# 8-Kanal-DIN-IN_V0.net
KiCad netlist of a schematic drawn in EAGLE
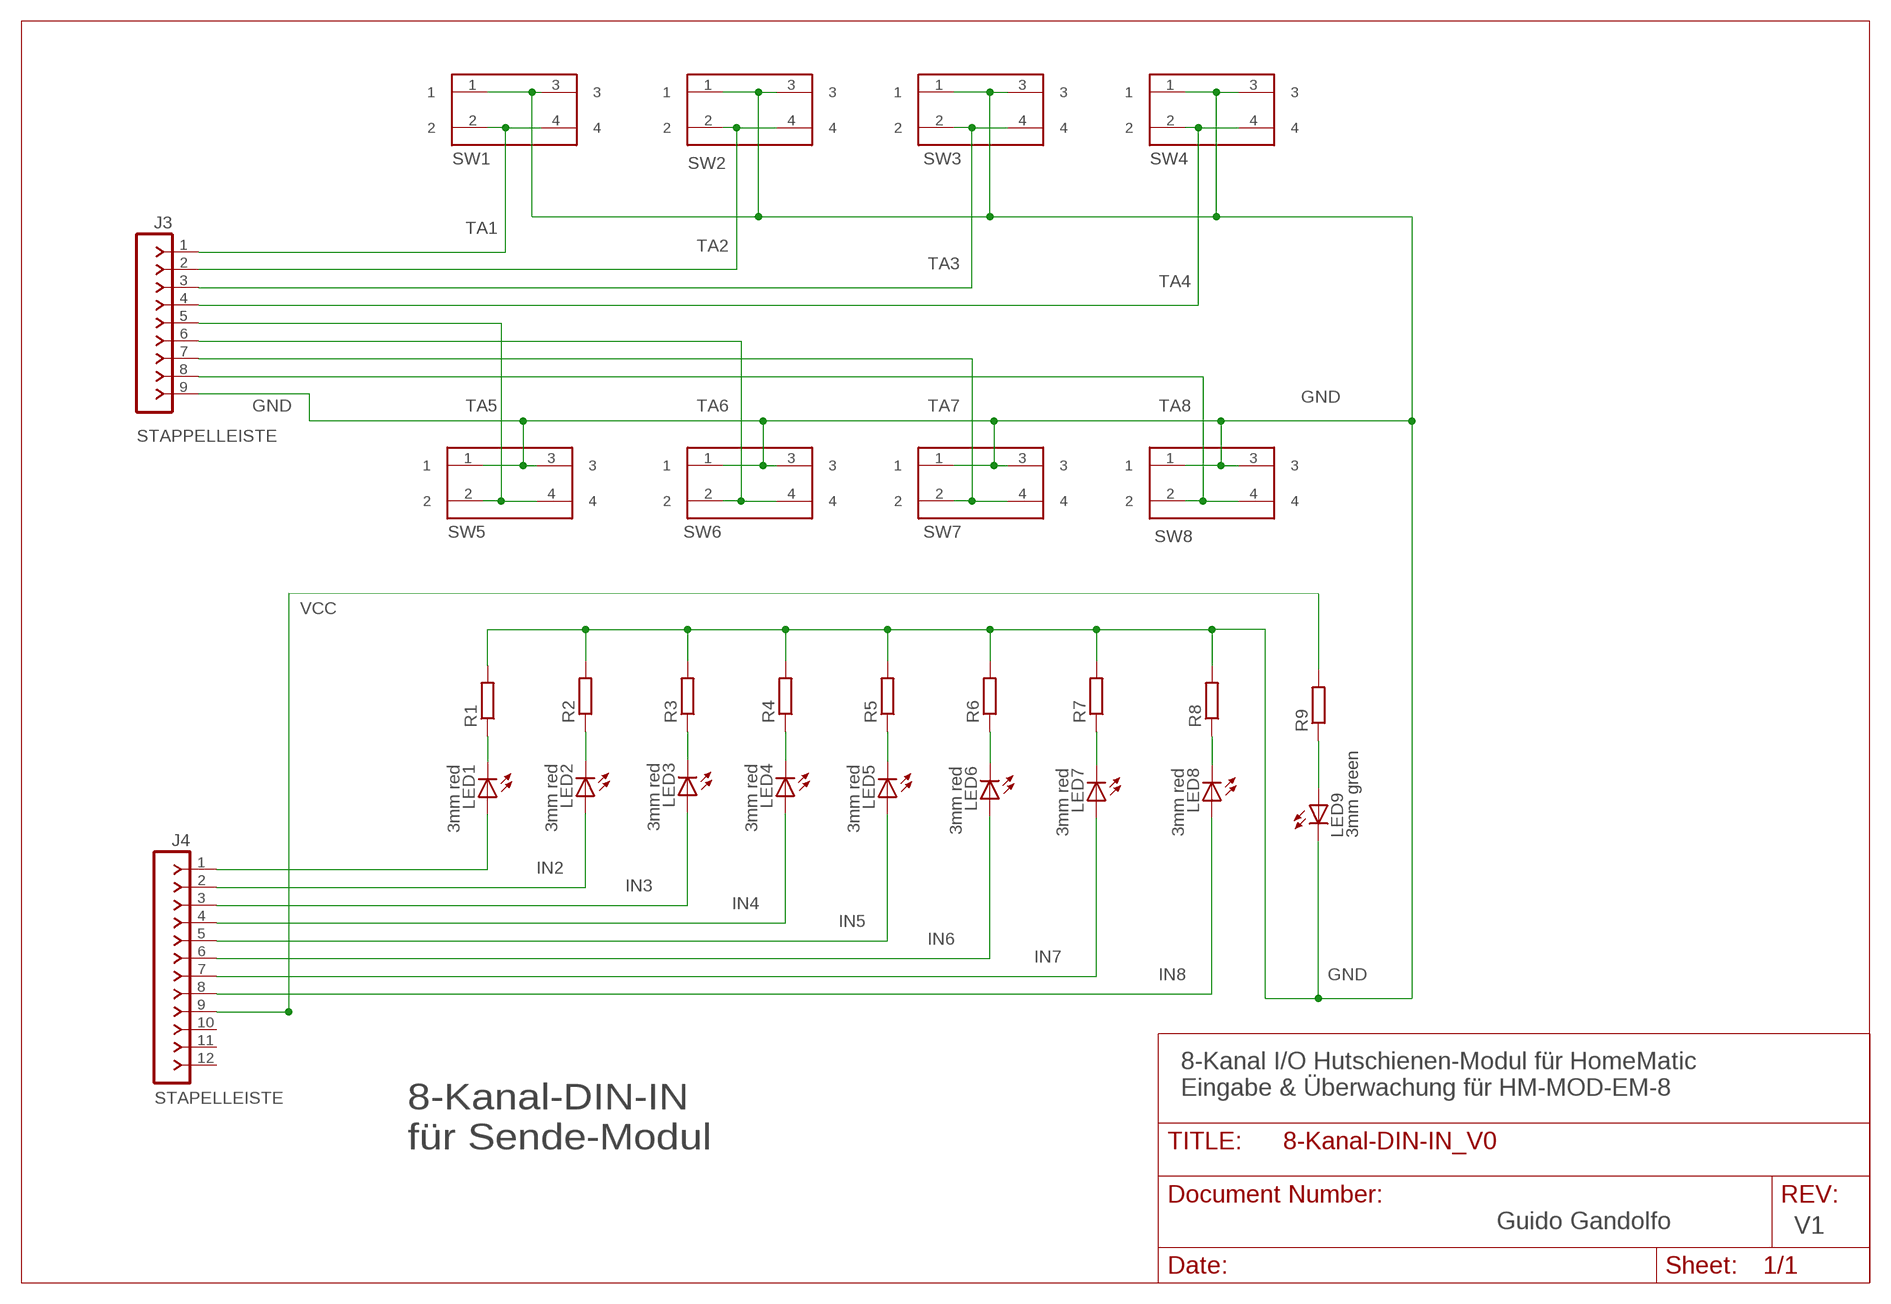
[diagram p0: schematic, sheet 1]

(export (version "E")
  (design (tool "Eeschema 10.0.6"))
  (components
    (comp (ref "J3")
      (value "STAPPELLEISTE")
      (footprint "eagle-import:SIP-100-09-40Y")
      (libsource (lib "eagle-import") (part "F-1X09-SIP-100-40Y"))
    )
    (comp (ref "J4")
      (value "STAPELLEISTE")
      (footprint "eagle-import:SIP-100-12-40Y")
      (libsource (lib "eagle-import") (part "F-1X12-SIP-100-40Y"))
    )
    (comp (ref "LED1")
      (value "3mm red")
      (footprint "eagle-import:LED3MM")
      (libsource (lib "eagle-import") (part "LED3MM"))
    )
    (comp (ref "LED2")
      (value "3mm red")
      (footprint "eagle-import:LED3MM")
      (libsource (lib "eagle-import") (part "LED3MM"))
    )
    (comp (ref "LED3")
      (value "3mm red")
      (footprint "eagle-import:LED3MM")
      (libsource (lib "eagle-import") (part "LED3MM"))
    )
    (comp (ref "LED4")
      (value "3mm red")
      (footprint "eagle-import:LED3MM")
      (libsource (lib "eagle-import") (part "LED3MM"))
    )
    (comp (ref "LED5")
      (value "3mm red")
      (footprint "eagle-import:LED3MM")
      (libsource (lib "eagle-import") (part "LED3MM"))
    )
    (comp (ref "LED6")
      (value "3mm red")
      (footprint "eagle-import:LED3MM")
      (libsource (lib "eagle-import") (part "LED3MM"))
    )
    (comp (ref "LED7")
      (value "3mm red")
      (footprint "eagle-import:LED3MM")
      (libsource (lib "eagle-import") (part "LED3MM"))
    )
    (comp (ref "LED8")
      (value "3mm red")
      (footprint "eagle-import:LED3MM")
      (libsource (lib "eagle-import") (part "LED3MM"))
    )
    (comp (ref "LED9")
      (value "3mm green")
      (footprint "eagle-import:LED3MM")
      (libsource (lib "eagle-import") (part "LED3MM"))
    )
    (comp (ref "R1")
      (value "R-EU_0207/2V")
      (footprint "eagle-import:0207_2V")
      (libsource (lib "eagle-import") (part "R-EU_0207/2V"))
    )
    (comp (ref "R2")
      (value "R-EU_0207/2V")
      (footprint "eagle-import:0207_2V")
      (libsource (lib "eagle-import") (part "R-EU_0207/2V"))
    )
    (comp (ref "R3")
      (value "R-EU_0207/2V")
      (footprint "eagle-import:0207_2V")
      (libsource (lib "eagle-import") (part "R-EU_0207/2V"))
    )
    (comp (ref "R4")
      (value "R-EU_0207/2V")
      (footprint "eagle-import:0207_2V")
      (libsource (lib "eagle-import") (part "R-EU_0207/2V"))
    )
    (comp (ref "R5")
      (value "R-EU_0207/2V")
      (footprint "eagle-import:0207_2V")
      (libsource (lib "eagle-import") (part "R-EU_0207/2V"))
    )
    (comp (ref "R6")
      (value "R-EU_0207/2V")
      (footprint "eagle-import:0207_2V")
      (libsource (lib "eagle-import") (part "R-EU_0207/2V"))
    )
    (comp (ref "R7")
      (value "R-EU_0207/2V")
      (footprint "eagle-import:0207_2V")
      (libsource (lib "eagle-import") (part "R-EU_0207/2V"))
    )
    (comp (ref "R8")
      (value "R-EU_0207/2V")
      (footprint "eagle-import:0207_2V")
      (libsource (lib "eagle-import") (part "R-EU_0207/2V"))
    )
    (comp (ref "R9")
      (value "R-EU_0207/2V")
      (footprint "eagle-import:0207_2V")
      (libsource (lib "eagle-import") (part "R-EU_0207/2V"))
    )
    (comp (ref "SW1")
      (value "TASTER 9305")
      (footprint "eagle-import:430156130936")
      (libsource (lib "eagle-import") (part "430156130936"))
    )
    (comp (ref "SW2")
      (value "TASTER 9305")
      (footprint "eagle-import:430156130936")
      (libsource (lib "eagle-import") (part "430156130936"))
    )
    (comp (ref "SW3")
      (value "TASTER 9305")
      (footprint "eagle-import:430156130936")
      (libsource (lib "eagle-import") (part "430156130936"))
    )
    (comp (ref "SW4")
      (value "TASTER 9305")
      (footprint "eagle-import:430156130936")
      (libsource (lib "eagle-import") (part "430156130936"))
    )
    (comp (ref "SW5")
      (value "TASTER 9305")
      (footprint "eagle-import:430156130936")
      (libsource (lib "eagle-import") (part "430156130936"))
    )
    (comp (ref "SW6")
      (value "TASTER 9305")
      (footprint "eagle-import:430156130936")
      (libsource (lib "eagle-import") (part "430156130936"))
    )
    (comp (ref "SW7")
      (value "TASTER 9305")
      (footprint "eagle-import:430156130936")
      (libsource (lib "eagle-import") (part "430156130936"))
    )
    (comp (ref "SW8")
      (value "TASTER 9305")
      (footprint "eagle-import:430156130936")
      (libsource (lib "eagle-import") (part "430156130936"))
    )
  )
  (nets
    (net (code "1") (name "/GND") (class "Default")
      (node (ref "J3") (pin "9") (pinfunction "9_9") (pintype "passive"))
      (node (ref "LED9") (pin "K") (pinfunction "C_K") (pintype "passive"))
      (node (ref "R1") (pin "2") (pinfunction "2_2") (pintype "passive"))
      (node (ref "R2") (pin "2") (pinfunction "2_2") (pintype "passive"))
      (node (ref "R3") (pin "2") (pinfunction "2_2") (pintype "passive"))
      (node (ref "R4") (pin "2") (pinfunction "2_2") (pintype "passive"))
      (node (ref "R5") (pin "2") (pinfunction "2_2") (pintype "passive"))
      (node (ref "R6") (pin "2") (pinfunction "2_2") (pintype "passive"))
      (node (ref "R7") (pin "2") (pinfunction "2_2") (pintype "passive"))
      (node (ref "R8") (pin "2") (pinfunction "2_2") (pintype "passive"))
      (node (ref "SW1") (pin "1") (pinfunction "1_1") (pintype "bidirectional"))
      (node (ref "SW1") (pin "3") (pinfunction "3_3") (pintype "bidirectional"))
      (node (ref "SW2") (pin "1") (pinfunction "1_1") (pintype "bidirectional"))
      (node (ref "SW2") (pin "3") (pinfunction "3_3") (pintype "bidirectional"))
      (node (ref "SW3") (pin "1") (pinfunction "1_1") (pintype "bidirectional"))
      (node (ref "SW3") (pin "3") (pinfunction "3_3") (pintype "bidirectional"))
      (node (ref "SW4") (pin "1") (pinfunction "1_1") (pintype "bidirectional"))
      (node (ref "SW4") (pin "3") (pinfunction "3_3") (pintype "bidirectional"))
      (node (ref "SW5") (pin "1") (pinfunction "1_1") (pintype "bidirectional"))
      (node (ref "SW5") (pin "3") (pinfunction "3_3") (pintype "bidirectional"))
      (node (ref "SW6") (pin "1") (pinfunction "1_1") (pintype "bidirectional"))
      (node (ref "SW6") (pin "3") (pinfunction "3_3") (pintype "bidirectional"))
      (node (ref "SW7") (pin "1") (pinfunction "1_1") (pintype "bidirectional"))
      (node (ref "SW7") (pin "3") (pinfunction "3_3") (pintype "bidirectional"))
      (node (ref "SW8") (pin "1") (pinfunction "1_1") (pintype "bidirectional"))
      (node (ref "SW8") (pin "3") (pinfunction "3_3") (pintype "bidirectional"))
    )
    (net (code "2") (name "/IN2") (class "Default")
      (node (ref "J4") (pin "2") (pinfunction "2_2") (pintype "passive"))
      (node (ref "LED2") (pin "A") (pinfunction "A_A") (pintype "passive"))
    )
    (net (code "3") (name "/IN3") (class "Default")
      (node (ref "J4") (pin "3") (pinfunction "3_3") (pintype "passive"))
      (node (ref "LED3") (pin "A") (pinfunction "A_A") (pintype "passive"))
    )
    (net (code "4") (name "/IN4") (class "Default")
      (node (ref "J4") (pin "4") (pinfunction "4_4") (pintype "passive"))
      (node (ref "LED4") (pin "A") (pinfunction "A_A") (pintype "passive"))
    )
    (net (code "5") (name "/IN5") (class "Default")
      (node (ref "J4") (pin "5") (pinfunction "5_5") (pintype "passive"))
      (node (ref "LED5") (pin "A") (pinfunction "A_A") (pintype "passive"))
    )
    (net (code "6") (name "/IN6") (class "Default")
      (node (ref "J4") (pin "6") (pinfunction "6_6") (pintype "passive"))
      (node (ref "LED6") (pin "A") (pinfunction "A_A") (pintype "passive"))
    )
    (net (code "7") (name "/IN7") (class "Default")
      (node (ref "J4") (pin "7") (pinfunction "7_7") (pintype "passive"))
      (node (ref "LED7") (pin "A") (pinfunction "A_A") (pintype "passive"))
    )
    (net (code "8") (name "/IN8") (class "Default")
      (node (ref "J4") (pin "8") (pinfunction "8_8") (pintype "passive"))
      (node (ref "LED8") (pin "A") (pinfunction "A_A") (pintype "passive"))
    )
    (net (code "9") (name "/TA1") (class "Default")
      (node (ref "J3") (pin "1") (pinfunction "1_1") (pintype "passive"))
      (node (ref "SW1") (pin "2") (pinfunction "2_2") (pintype "bidirectional"))
      (node (ref "SW1") (pin "4") (pinfunction "4_4") (pintype "bidirectional"))
    )
    (net (code "10") (name "/TA2") (class "Default")
      (node (ref "J3") (pin "2") (pinfunction "2_2") (pintype "passive"))
      (node (ref "SW2") (pin "2") (pinfunction "2_2") (pintype "bidirectional"))
      (node (ref "SW2") (pin "4") (pinfunction "4_4") (pintype "bidirectional"))
    )
    (net (code "11") (name "/TA3") (class "Default")
      (node (ref "J3") (pin "3") (pinfunction "3_3") (pintype "passive"))
      (node (ref "SW3") (pin "2") (pinfunction "2_2") (pintype "bidirectional"))
      (node (ref "SW3") (pin "4") (pinfunction "4_4") (pintype "bidirectional"))
    )
    (net (code "12") (name "/TA4") (class "Default")
      (node (ref "J3") (pin "4") (pinfunction "4_4") (pintype "passive"))
      (node (ref "SW4") (pin "2") (pinfunction "2_2") (pintype "bidirectional"))
      (node (ref "SW4") (pin "4") (pinfunction "4_4") (pintype "bidirectional"))
    )
    (net (code "13") (name "/TA5") (class "Default")
      (node (ref "J3") (pin "5") (pinfunction "5_5") (pintype "passive"))
      (node (ref "SW5") (pin "2") (pinfunction "2_2") (pintype "bidirectional"))
      (node (ref "SW5") (pin "4") (pinfunction "4_4") (pintype "bidirectional"))
    )
    (net (code "14") (name "/TA6") (class "Default")
      (node (ref "J3") (pin "6") (pinfunction "6_6") (pintype "passive"))
      (node (ref "SW6") (pin "2") (pinfunction "2_2") (pintype "bidirectional"))
      (node (ref "SW6") (pin "4") (pinfunction "4_4") (pintype "bidirectional"))
    )
    (net (code "15") (name "/TA7") (class "Default")
      (node (ref "J3") (pin "7") (pinfunction "7_7") (pintype "passive"))
      (node (ref "SW7") (pin "2") (pinfunction "2_2") (pintype "bidirectional"))
      (node (ref "SW7") (pin "4") (pinfunction "4_4") (pintype "bidirectional"))
    )
    (net (code "16") (name "/TA8") (class "Default")
      (node (ref "J3") (pin "8") (pinfunction "8_8") (pintype "passive"))
      (node (ref "SW8") (pin "2") (pinfunction "2_2") (pintype "bidirectional"))
      (node (ref "SW8") (pin "4") (pinfunction "4_4") (pintype "bidirectional"))
    )
    (net (code "17") (name "/VCC") (class "Default")
      (node (ref "J4") (pin "9") (pinfunction "9_9") (pintype "passive"))
      (node (ref "R9") (pin "2") (pinfunction "2_2") (pintype "passive"))
    )
    (net (code "18") (name "Net-(J4-Pad1)") (class "Default")
      (node (ref "J4") (pin "1") (pinfunction "1_1") (pintype "passive"))
      (node (ref "LED1") (pin "A") (pinfunction "A_A") (pintype "passive"))
    )
    (net (code "19") (name "Net-(LED1-C)") (class "Default")
      (node (ref "LED1") (pin "K") (pinfunction "C_K") (pintype "passive"))
      (node (ref "R1") (pin "1") (pinfunction "1_1") (pintype "passive"))
    )
    (net (code "20") (name "Net-(LED2-C)") (class "Default")
      (node (ref "LED2") (pin "K") (pinfunction "C_K") (pintype "passive"))
      (node (ref "R2") (pin "1") (pinfunction "1_1") (pintype "passive"))
    )
    (net (code "21") (name "Net-(LED3-C)") (class "Default")
      (node (ref "LED3") (pin "K") (pinfunction "C_K") (pintype "passive"))
      (node (ref "R3") (pin "1") (pinfunction "1_1") (pintype "passive"))
    )
    (net (code "22") (name "Net-(LED4-C)") (class "Default")
      (node (ref "LED4") (pin "K") (pinfunction "C_K") (pintype "passive"))
      (node (ref "R4") (pin "1") (pinfunction "1_1") (pintype "passive"))
    )
    (net (code "23") (name "Net-(LED5-C)") (class "Default")
      (node (ref "LED5") (pin "K") (pinfunction "C_K") (pintype "passive"))
      (node (ref "R5") (pin "1") (pinfunction "1_1") (pintype "passive"))
    )
    (net (code "24") (name "Net-(LED6-C)") (class "Default")
      (node (ref "LED6") (pin "K") (pinfunction "C_K") (pintype "passive"))
      (node (ref "R6") (pin "1") (pinfunction "1_1") (pintype "passive"))
    )
    (net (code "25") (name "Net-(LED7-C)") (class "Default")
      (node (ref "LED7") (pin "K") (pinfunction "C_K") (pintype "passive"))
      (node (ref "R7") (pin "1") (pinfunction "1_1") (pintype "passive"))
    )
    (net (code "26") (name "Net-(LED8-C)") (class "Default")
      (node (ref "LED8") (pin "K") (pinfunction "C_K") (pintype "passive"))
      (node (ref "R8") (pin "1") (pinfunction "1_1") (pintype "passive"))
    )
    (net (code "27") (name "Net-(LED9-PadA)") (class "Default")
      (node (ref "LED9") (pin "A") (pinfunction "A_A") (pintype "passive"))
      (node (ref "R9") (pin "1") (pinfunction "1_1") (pintype "passive"))
    )
    (net (code "28") (name "unconnected-(J4-Pad10)") (class "Default")
      (node (ref "J4") (pin "10") (pinfunction "10_10") (pintype "passive"))
    )
    (net (code "29") (name "unconnected-(J4-Pad11)") (class "Default")
      (node (ref "J4") (pin "11") (pinfunction "11_11") (pintype "passive"))
    )
    (net (code "30") (name "unconnected-(J4-Pad12)") (class "Default")
      (node (ref "J4") (pin "12") (pinfunction "12_12") (pintype "passive"))
    )
  )
)
